# 2PCB-Part1.net
KiCad netlist of a schematic drawn in EAGLE
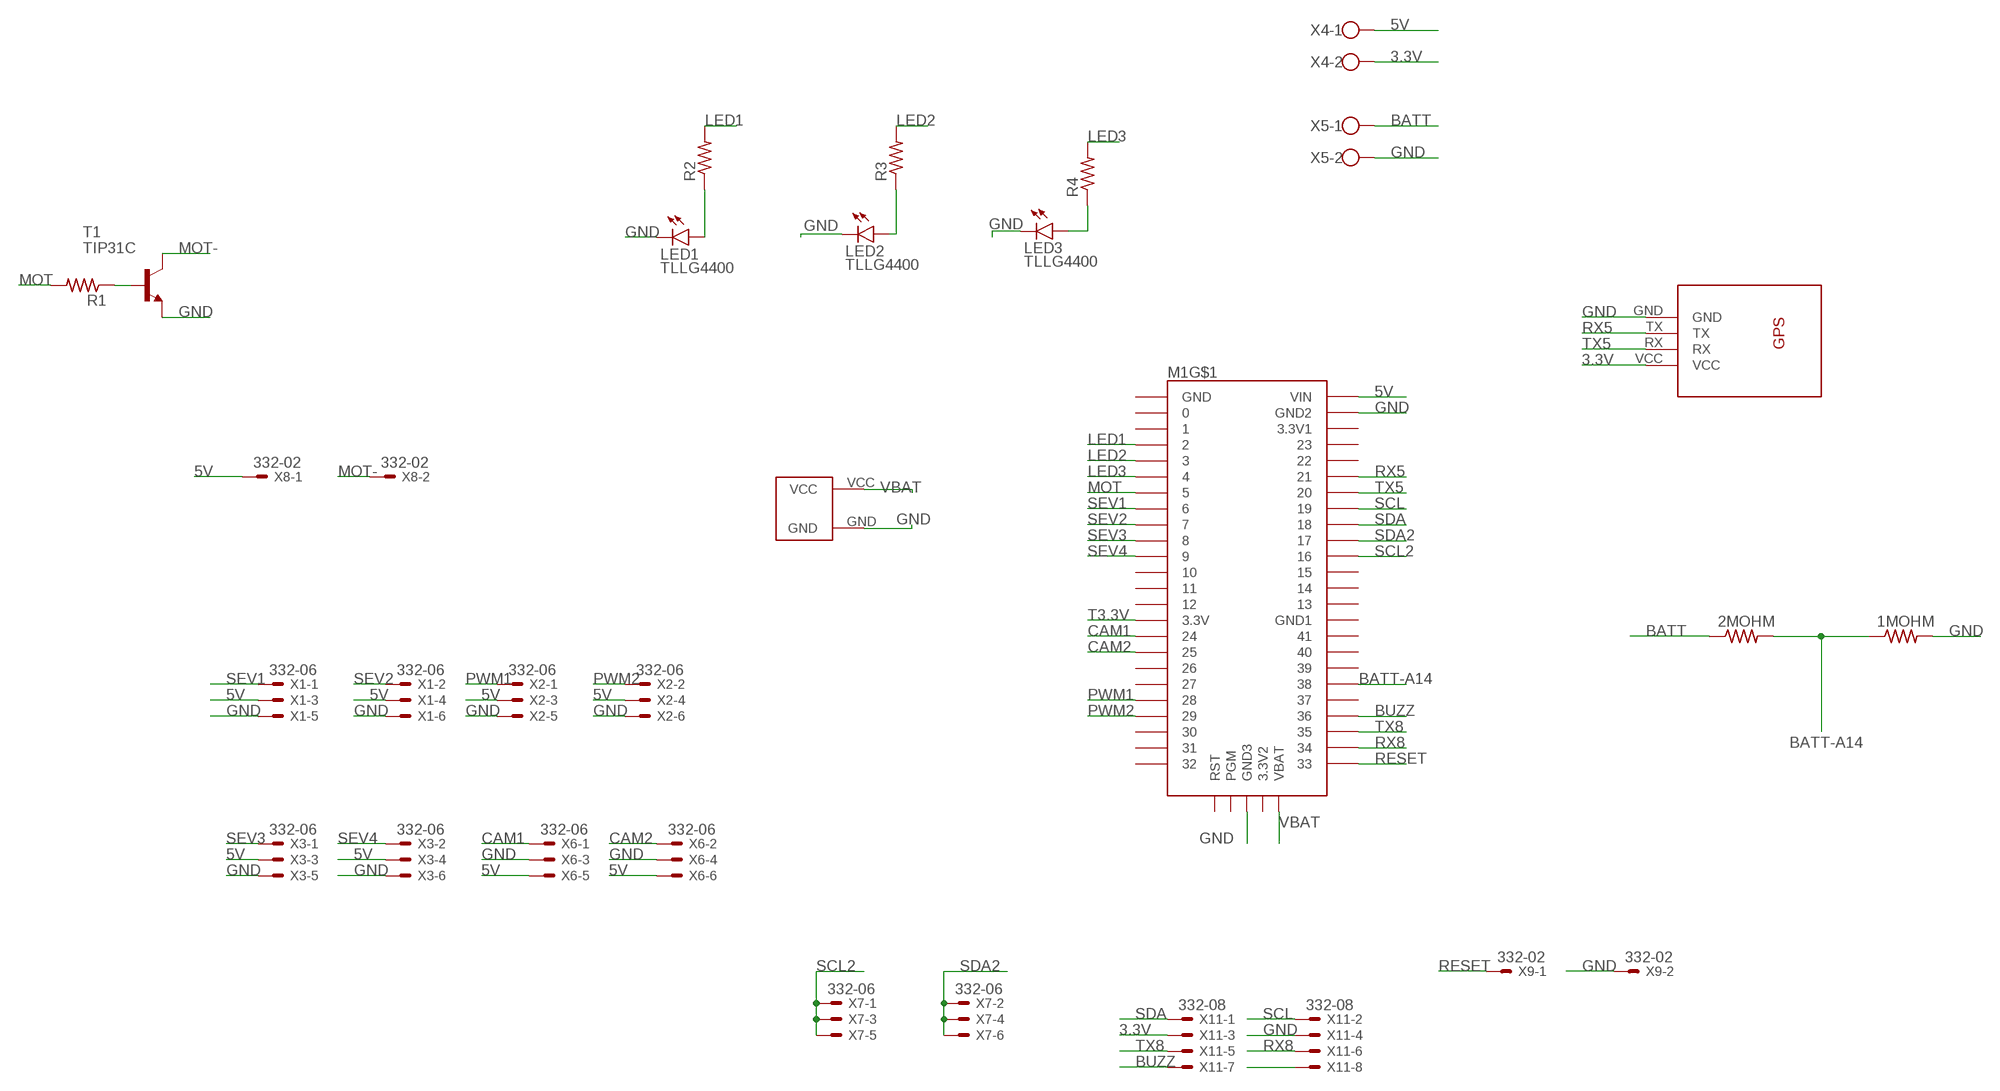
[diagram p0: schematic, sheet 1]

(export (version "E")
  (design (tool "Eeschema 10.0.6"))
  (components
    (comp (ref "1MOHM")
      (value "R-US_0207/10")
      (footprint "eagle-import:0207_10")
      (libsource (lib "eagle-import") (part "R-US_0207/10"))
    )
    (comp (ref "2MOHM")
      (value "R-US_0207/10")
      (footprint "eagle-import:0207_10")
      (libsource (lib "eagle-import") (part "R-US_0207/10"))
    )
    (comp (ref "LED1")
      (value "TLLG4400")
      (footprint "eagle-import:LED3MM")
      (fields (field (name "MF") "VISHAY SEMICONDUCTOR"))
      (libsource (lib "eagle-import") (part "TLLG4400"))
    )
    (comp (ref "LED2")
      (value "TLLG4400")
      (footprint "eagle-import:LED3MM")
      (fields (field (name "MF") "VISHAY SEMICONDUCTOR"))
      (libsource (lib "eagle-import") (part "TLLG4400"))
    )
    (comp (ref "LED3")
      (value "TLLG4400")
      (footprint "eagle-import:LED3MM")
      (fields (field (name "MF") "VISHAY SEMICONDUCTOR"))
      (libsource (lib "eagle-import") (part "TLLG4400"))
    )
    (comp (ref "M1")
      (value "TEENSY4.1")
      (footprint "eagle-import:TEENSY4.1")
      (libsource (lib "eagle-import") (part "TEENSY4.1"))
    )
    (comp (ref "R1")
      (value "R-US_0207/10")
      (footprint "eagle-import:0207_10")
      (libsource (lib "eagle-import") (part "R-US_0207/10"))
    )
    (comp (ref "R2")
      (value "R-US_0207/10")
      (footprint "eagle-import:0207_10")
      (libsource (lib "eagle-import") (part "R-US_0207/10"))
    )
    (comp (ref "R3")
      (value "R-US_0207/10")
      (footprint "eagle-import:0207_10")
      (libsource (lib "eagle-import") (part "R-US_0207/10"))
    )
    (comp (ref "R4")
      (value "R-US_0207/10")
      (footprint "eagle-import:0207_10")
      (libsource (lib "eagle-import") (part "R-US_0207/10"))
    )
    (comp (ref "T1")
      (value "TIP31C")
      (footprint "eagle-import:TO220")
      (libsource (lib "eagle-import") (part "TIP31C"))
    )
    (comp (ref "U$1")
      (value "GPS")
      (footprint "eagle-import:GPS")
      (libsource (lib "eagle-import") (part "GPS"))
    )
    (comp (ref "U$2")
      (value "CR2032")
      (footprint "eagle-import:CR2032-20MM")
      (libsource (lib "eagle-import") (part "CR2032"))
    )
    (comp (ref "X1")
      (value "332-06")
      (footprint "eagle-import:332-06")
      (libsource (lib "eagle-import") (part "332-06"))
    )
    (comp (ref "X2")
      (value "332-06")
      (footprint "eagle-import:332-06")
      (libsource (lib "eagle-import") (part "332-06"))
    )
    (comp (ref "X3")
      (value "332-06")
      (footprint "eagle-import:332-06")
      (libsource (lib "eagle-import") (part "332-06"))
    )
    (comp (ref "X4")
      (value "W237-102")
      (footprint "eagle-import:W237-102")
      (fields (field (name "MPN") "237-102"))
      (libsource (lib "eagle-import") (part "W237-102"))
    )
    (comp (ref "X5")
      (value "W237-102")
      (footprint "eagle-import:W237-102")
      (fields (field (name "MPN") "237-102"))
      (libsource (lib "eagle-import") (part "W237-102"))
    )
    (comp (ref "X6")
      (value "332-06")
      (footprint "eagle-import:332-06")
      (libsource (lib "eagle-import") (part "332-06"))
    )
    (comp (ref "X7")
      (value "332-06")
      (footprint "eagle-import:332-06")
      (libsource (lib "eagle-import") (part "332-06"))
    )
    (comp (ref "X8")
      (value "332-02")
      (footprint "eagle-import:332-02")
      (libsource (lib "eagle-import") (part "332-02"))
    )
    (comp (ref "X9")
      (value "332-02")
      (footprint "eagle-import:332-02")
      (libsource (lib "eagle-import") (part "332-02"))
    )
    (comp (ref "X11")
      (value "332-08")
      (footprint "eagle-import:332-08")
      (libsource (lib "eagle-import") (part "332-08"))
    )
  )
  (nets
    (net (code "1") (name "/3.3V") (class "Default")
      (node (ref "U$1") (pin "VCC") (pinfunction "VCC_VCC") (pintype "bidirectional"))
      (node (ref "X11") (pin "3") (pinfunction "S_3") (pintype "passive"))
      (node (ref "X4") (pin "2") (pinfunction "KL_2") (pintype "passive"))
    )
    (net (code "2") (name "/5V") (class "Default")
      (node (ref "M1") (pin "VIN") (pinfunction "VIN_VIN") (pintype "bidirectional"))
      (node (ref "X1") (pin "3") (pinfunction "S_3") (pintype "passive"))
      (node (ref "X1") (pin "4") (pinfunction "S_4") (pintype "passive"))
      (node (ref "X2") (pin "3") (pinfunction "S_3") (pintype "passive"))
      (node (ref "X2") (pin "4") (pinfunction "S_4") (pintype "passive"))
      (node (ref "X3") (pin "3") (pinfunction "S_3") (pintype "passive"))
      (node (ref "X3") (pin "4") (pinfunction "S_4") (pintype "passive"))
      (node (ref "X4") (pin "1") (pinfunction "KL_1") (pintype "passive"))
      (node (ref "X6") (pin "5") (pinfunction "S_5") (pintype "passive"))
      (node (ref "X6") (pin "6") (pinfunction "S_6") (pintype "passive"))
      (node (ref "X8") (pin "1") (pinfunction "S_1") (pintype "passive"))
    )
    (net (code "3") (name "/BATT") (class "Default")
      (node (ref "2MOHM") (pin "1") (pinfunction "1_1") (pintype "passive"))
      (node (ref "X5") (pin "1") (pinfunction "KL_1") (pintype "passive"))
    )
    (net (code "4") (name "/BATT-A14") (class "Default")
      (node (ref "1MOHM") (pin "1") (pinfunction "1_1") (pintype "passive"))
      (node (ref "2MOHM") (pin "2") (pinfunction "2_2") (pintype "passive"))
      (node (ref "M1") (pin "38") (pinfunction "38_38") (pintype "bidirectional"))
    )
    (net (code "5") (name "/BUZZ") (class "Default")
      (node (ref "M1") (pin "36") (pinfunction "36_36") (pintype "bidirectional"))
      (node (ref "X11") (pin "7") (pinfunction "S_7") (pintype "passive"))
    )
    (net (code "6") (name "/CAM1") (class "Default")
      (node (ref "M1") (pin "24") (pinfunction "24_24") (pintype "bidirectional"))
      (node (ref "X6") (pin "1") (pinfunction "S_1") (pintype "passive"))
    )
    (net (code "7") (name "/CAM2") (class "Default")
      (node (ref "M1") (pin "25") (pinfunction "25_25") (pintype "bidirectional"))
      (node (ref "X6") (pin "2") (pinfunction "S_2") (pintype "passive"))
    )
    (net (code "8") (name "/GND") (class "Default")
      (node (ref "1MOHM") (pin "2") (pinfunction "2_2") (pintype "passive"))
      (node (ref "LED1") (pin "K") (pinfunction "C_K") (pintype "passive"))
      (node (ref "LED2") (pin "K") (pinfunction "C_K") (pintype "passive"))
      (node (ref "LED3") (pin "K") (pinfunction "C_K") (pintype "passive"))
      (node (ref "M1") (pin "AGND") (pinfunction "GND2_AGND") (pintype "bidirectional"))
      (node (ref "M1") (pin "GND2") (pinfunction "GND3_GND2") (pintype "bidirectional"))
      (node (ref "T1") (pin "3") (pinfunction "E_3") (pintype "passive"))
      (node (ref "U$1") (pin "GND") (pinfunction "GND_GND") (pintype "bidirectional"))
      (node (ref "U$2") (pin "GND") (pinfunction "GND_GND") (pintype "bidirectional"))
      (node (ref "X1") (pin "5") (pinfunction "S_5") (pintype "passive"))
      (node (ref "X1") (pin "6") (pinfunction "S_6") (pintype "passive"))
      (node (ref "X11") (pin "4") (pinfunction "S_4") (pintype "passive"))
      (node (ref "X2") (pin "5") (pinfunction "S_5") (pintype "passive"))
      (node (ref "X2") (pin "6") (pinfunction "S_6") (pintype "passive"))
      (node (ref "X3") (pin "5") (pinfunction "S_5") (pintype "passive"))
      (node (ref "X3") (pin "6") (pinfunction "S_6") (pintype "passive"))
      (node (ref "X5") (pin "2") (pinfunction "KL_2") (pintype "passive"))
      (node (ref "X6") (pin "3") (pinfunction "S_3") (pintype "passive"))
      (node (ref "X6") (pin "4") (pinfunction "S_4") (pintype "passive"))
      (node (ref "X9") (pin "2") (pinfunction "S_2") (pintype "passive"))
    )
    (net (code "9") (name "/LED1") (class "Default")
      (node (ref "M1") (pin "2") (pinfunction "2_2") (pintype "bidirectional"))
      (node (ref "R2") (pin "2") (pinfunction "2_2") (pintype "passive"))
    )
    (net (code "10") (name "/LED2") (class "Default")
      (node (ref "M1") (pin "3") (pinfunction "3_3") (pintype "bidirectional"))
      (node (ref "R3") (pin "2") (pinfunction "2_2") (pintype "passive"))
    )
    (net (code "11") (name "/LED3") (class "Default")
      (node (ref "M1") (pin "4") (pinfunction "4_4") (pintype "bidirectional"))
      (node (ref "R4") (pin "2") (pinfunction "2_2") (pintype "passive"))
    )
    (net (code "12") (name "/MOT") (class "Default")
      (node (ref "M1") (pin "5") (pinfunction "5_5") (pintype "bidirectional"))
      (node (ref "R1") (pin "2") (pinfunction "2_2") (pintype "passive"))
    )
    (net (code "13") (name "/MOT-") (class "Default")
      (node (ref "T1") (pin "2") (pinfunction "C_2") (pintype "passive"))
      (node (ref "X8") (pin "2") (pinfunction "S_2") (pintype "passive"))
    )
    (net (code "14") (name "/PWM1") (class "Default")
      (node (ref "M1") (pin "28") (pinfunction "28_28") (pintype "bidirectional"))
      (node (ref "X2") (pin "1") (pinfunction "S_1") (pintype "passive"))
    )
    (net (code "15") (name "/PWM2") (class "Default")
      (node (ref "M1") (pin "29") (pinfunction "29_29") (pintype "bidirectional"))
      (node (ref "X2") (pin "2") (pinfunction "S_2") (pintype "passive"))
    )
    (net (code "16") (name "/RESET") (class "Default")
      (node (ref "M1") (pin "33") (pinfunction "33_33") (pintype "bidirectional"))
      (node (ref "X9") (pin "1") (pinfunction "S_1") (pintype "passive"))
    )
    (net (code "17") (name "/RX5") (class "Default")
      (node (ref "M1") (pin "21/A7") (pinfunction "21_21/A7") (pintype "bidirectional"))
      (node (ref "U$1") (pin "TX") (pinfunction "TX_TX") (pintype "bidirectional"))
    )
    (net (code "18") (name "/RX8") (class "Default")
      (node (ref "M1") (pin "34") (pinfunction "34_34") (pintype "bidirectional"))
      (node (ref "X11") (pin "6") (pinfunction "S_6") (pintype "passive"))
    )
    (net (code "19") (name "/SCL") (class "Default")
      (node (ref "M1") (pin "19/A5/SCL") (pinfunction "19_19/A5/SCL") (pintype "bidirectional"))
      (node (ref "X11") (pin "2") (pinfunction "S_2") (pintype "passive"))
    )
    (net (code "20") (name "/SCL2") (class "Default")
      (node (ref "M1") (pin "16/A2") (pinfunction "16_16/A2") (pintype "bidirectional"))
      (node (ref "X7") (pin "1") (pinfunction "S_1") (pintype "passive"))
      (node (ref "X7") (pin "3") (pinfunction "S_3") (pintype "passive"))
      (node (ref "X7") (pin "5") (pinfunction "S_5") (pintype "passive"))
    )
    (net (code "21") (name "/SDA") (class "Default")
      (node (ref "M1") (pin "18/A4/SDA") (pinfunction "18_18/A4/SDA") (pintype "bidirectional"))
      (node (ref "X11") (pin "1") (pinfunction "S_1") (pintype "passive"))
    )
    (net (code "22") (name "/SDA2") (class "Default")
      (node (ref "M1") (pin "17/A3") (pinfunction "17_17/A3") (pintype "bidirectional"))
      (node (ref "X7") (pin "2") (pinfunction "S_2") (pintype "passive"))
      (node (ref "X7") (pin "4") (pinfunction "S_4") (pintype "passive"))
      (node (ref "X7") (pin "6") (pinfunction "S_6") (pintype "passive"))
    )
    (net (code "23") (name "/SEV1") (class "Default")
      (node (ref "M1") (pin "6") (pinfunction "6_6") (pintype "bidirectional"))
      (node (ref "X1") (pin "1") (pinfunction "S_1") (pintype "passive"))
    )
    (net (code "24") (name "/SEV2") (class "Default")
      (node (ref "M1") (pin "7") (pinfunction "7_7") (pintype "bidirectional"))
      (node (ref "X1") (pin "2") (pinfunction "S_2") (pintype "passive"))
    )
    (net (code "25") (name "/SEV3") (class "Default")
      (node (ref "M1") (pin "8") (pinfunction "8_8") (pintype "bidirectional"))
      (node (ref "X3") (pin "1") (pinfunction "S_1") (pintype "passive"))
    )
    (net (code "26") (name "/SEV4") (class "Default")
      (node (ref "M1") (pin "9") (pinfunction "9_9") (pintype "bidirectional"))
      (node (ref "X3") (pin "2") (pinfunction "S_2") (pintype "passive"))
    )
    (net (code "27") (name "/T3.3V") (class "Default")
      (node (ref "M1") (pin "3V3") (pinfunction "3.3V_3V3") (pintype "bidirectional"))
    )
    (net (code "28") (name "/TX5") (class "Default")
      (node (ref "M1") (pin "20/A6") (pinfunction "20_20/A6") (pintype "bidirectional"))
      (node (ref "U$1") (pin "RX") (pinfunction "RX_RX") (pintype "bidirectional"))
    )
    (net (code "29") (name "/TX8") (class "Default")
      (node (ref "M1") (pin "35") (pinfunction "35_35") (pintype "bidirectional"))
      (node (ref "X11") (pin "5") (pinfunction "S_5") (pintype "passive"))
    )
    (net (code "30") (name "/VBAT") (class "Default")
      (node (ref "M1") (pin "VBAT") (pinfunction "VBAT_VBAT") (pintype "bidirectional"))
      (node (ref "U$2") (pin "VCC") (pinfunction "VCC_VCC") (pintype "bidirectional"))
    )
    (net (code "31") (name "Net-(LED1-PadA)") (class "Default")
      (node (ref "LED1") (pin "A") (pinfunction "A_A") (pintype "passive"))
      (node (ref "R2") (pin "1") (pinfunction "1_1") (pintype "passive"))
    )
    (net (code "32") (name "Net-(LED2-PadA)") (class "Default")
      (node (ref "LED2") (pin "A") (pinfunction "A_A") (pintype "passive"))
      (node (ref "R3") (pin "1") (pinfunction "1_1") (pintype "passive"))
    )
    (net (code "33") (name "Net-(LED3-PadA)") (class "Default")
      (node (ref "LED3") (pin "A") (pinfunction "A_A") (pintype "passive"))
      (node (ref "R4") (pin "1") (pinfunction "1_1") (pintype "passive"))
    )
    (net (code "34") (name "Net-(T1-B)") (class "Default")
      (node (ref "R1") (pin "1") (pinfunction "1_1") (pintype "passive"))
      (node (ref "T1") (pin "1") (pinfunction "B_1") (pintype "passive"))
    )
    (net (code "35") (name "unconnected-(M1-Pad26)") (class "Default")
      (node (ref "M1") (pin "26") (pinfunction "26_26") (pintype "bidirectional"))
    )
    (net (code "36") (name "unconnected-(M1-Pad27)") (class "Default")
      (node (ref "M1") (pin "27") (pinfunction "27_27") (pintype "bidirectional"))
    )
    (net (code "37") (name "unconnected-(M1-Pad30)") (class "Default")
      (node (ref "M1") (pin "30") (pinfunction "30_30") (pintype "bidirectional"))
    )
    (net (code "38") (name "unconnected-(M1-Pad32)") (class "Default")
      (node (ref "M1") (pin "32") (pinfunction "32_32") (pintype "bidirectional"))
    )
    (net (code "39") (name "unconnected-(M1-Pad37)") (class "Default")
      (node (ref "M1") (pin "37") (pinfunction "37_37") (pintype "bidirectional"))
    )
    (net (code "40") (name "unconnected-(M1-Pad39)") (class "Default")
      (node (ref "M1") (pin "39") (pinfunction "39_39") (pintype "bidirectional"))
    )
    (net (code "41") (name "unconnected-(M1-Pad40)") (class "Default")
      (node (ref "M1") (pin "40") (pinfunction "40_40") (pintype "bidirectional"))
    )
    (net (code "42") (name "unconnected-(M1-Pad41)") (class "Default")
      (node (ref "M1") (pin "41") (pinfunction "41_41") (pintype "bidirectional"))
    )
    (net (code "43") (name "unconnected-(M1-PadGND)") (class "Default")
      (node (ref "M1") (pin "GND") (pinfunction "GND_GND") (pintype "bidirectional"))
    )
    (net (code "44") (name "unconnected-(M1-PadGND1)") (class "Default")
      (node (ref "M1") (pin "GND1") (pinfunction "GND1_GND1") (pintype "bidirectional"))
    )
    (net (code "45") (name "unconnected-(M1-PadRST)") (class "Default")
      (node (ref "M1") (pin "RST") (pinfunction "RST_RST") (pintype "bidirectional"))
    )
    (net (code "46") (name "unconnected-(M1A-0-Pad0{slash}RX)") (class "Default")
      (node (ref "M1") (pin "0/RX") (pinfunction "0_0/RX") (pintype "bidirectional"))
    )
    (net (code "47") (name "unconnected-(M1A-1-Pad1{slash}TX)") (class "Default")
      (node (ref "M1") (pin "1/TX") (pinfunction "1_1/TX") (pintype "bidirectional"))
    )
    (net (code "48") (name "unconnected-(M1A-3.3V1-Pad3V3_LO)") (class "Default")
      (node (ref "M1") (pin "3V3_LO") (pinfunction "3.3V1_3V3_LO") (pintype "bidirectional"))
    )
    (net (code "49") (name "unconnected-(M1A-3.3V2-PadV33)") (class "Default")
      (node (ref "M1") (pin "V33") (pinfunction "3.3V2_V33") (pintype "bidirectional"))
    )
    (net (code "50") (name "unconnected-(M1A-10-Pad10{slash}CS)") (class "Default")
      (node (ref "M1") (pin "10/CS") (pinfunction "10_10/CS") (pintype "bidirectional"))
    )
    (net (code "51") (name "unconnected-(M1A-11-Pad11{slash}MOSI)") (class "Default")
      (node (ref "M1") (pin "11/MOSI") (pinfunction "11_11/MOSI") (pintype "bidirectional"))
    )
    (net (code "52") (name "unconnected-(M1A-12-Pad12{slash}MISO)") (class "Default")
      (node (ref "M1") (pin "12/MISO") (pinfunction "12_12/MISO") (pintype "bidirectional"))
    )
    (net (code "53") (name "unconnected-(M1A-13-Pad13{slash}SCK)") (class "Default")
      (node (ref "M1") (pin "13/SCK") (pinfunction "13_13/SCK") (pintype "bidirectional"))
    )
    (net (code "54") (name "unconnected-(M1A-14-Pad14{slash}A0)") (class "Default")
      (node (ref "M1") (pin "14/A0") (pinfunction "14_14/A0") (pintype "bidirectional"))
    )
    (net (code "55") (name "unconnected-(M1A-15-Pad15{slash}A1)") (class "Default")
      (node (ref "M1") (pin "15/A1") (pinfunction "15_15/A1") (pintype "bidirectional"))
    )
    (net (code "56") (name "unconnected-(M1A-22-Pad22{slash}A8)") (class "Default")
      (node (ref "M1") (pin "22/A8") (pinfunction "22_22/A8") (pintype "bidirectional"))
    )
    (net (code "57") (name "unconnected-(M1A-23-Pad23{slash}A9)") (class "Default")
      (node (ref "M1") (pin "23/A9") (pinfunction "23_23/A9") (pintype "bidirectional"))
    )
    (net (code "58") (name "unconnected-(M1A-31-Pad31{slash}A12)") (class "Default")
      (node (ref "M1") (pin "31/A12") (pinfunction "31_31/A12") (pintype "bidirectional"))
    )
    (net (code "59") (name "unconnected-(M1A-PGM-PadPROG)") (class "Default")
      (node (ref "M1") (pin "PROG") (pinfunction "PGM_PROG") (pintype "bidirectional"))
    )
    (net (code "60") (name "unconnected-(X11H-S-Pad8)") (class "Default")
      (node (ref "X11") (pin "8") (pinfunction "S_8") (pintype "passive"))
    )
  )
)
